# schematic.net
KiCad netlist of a schematic drawn in Altium Designer
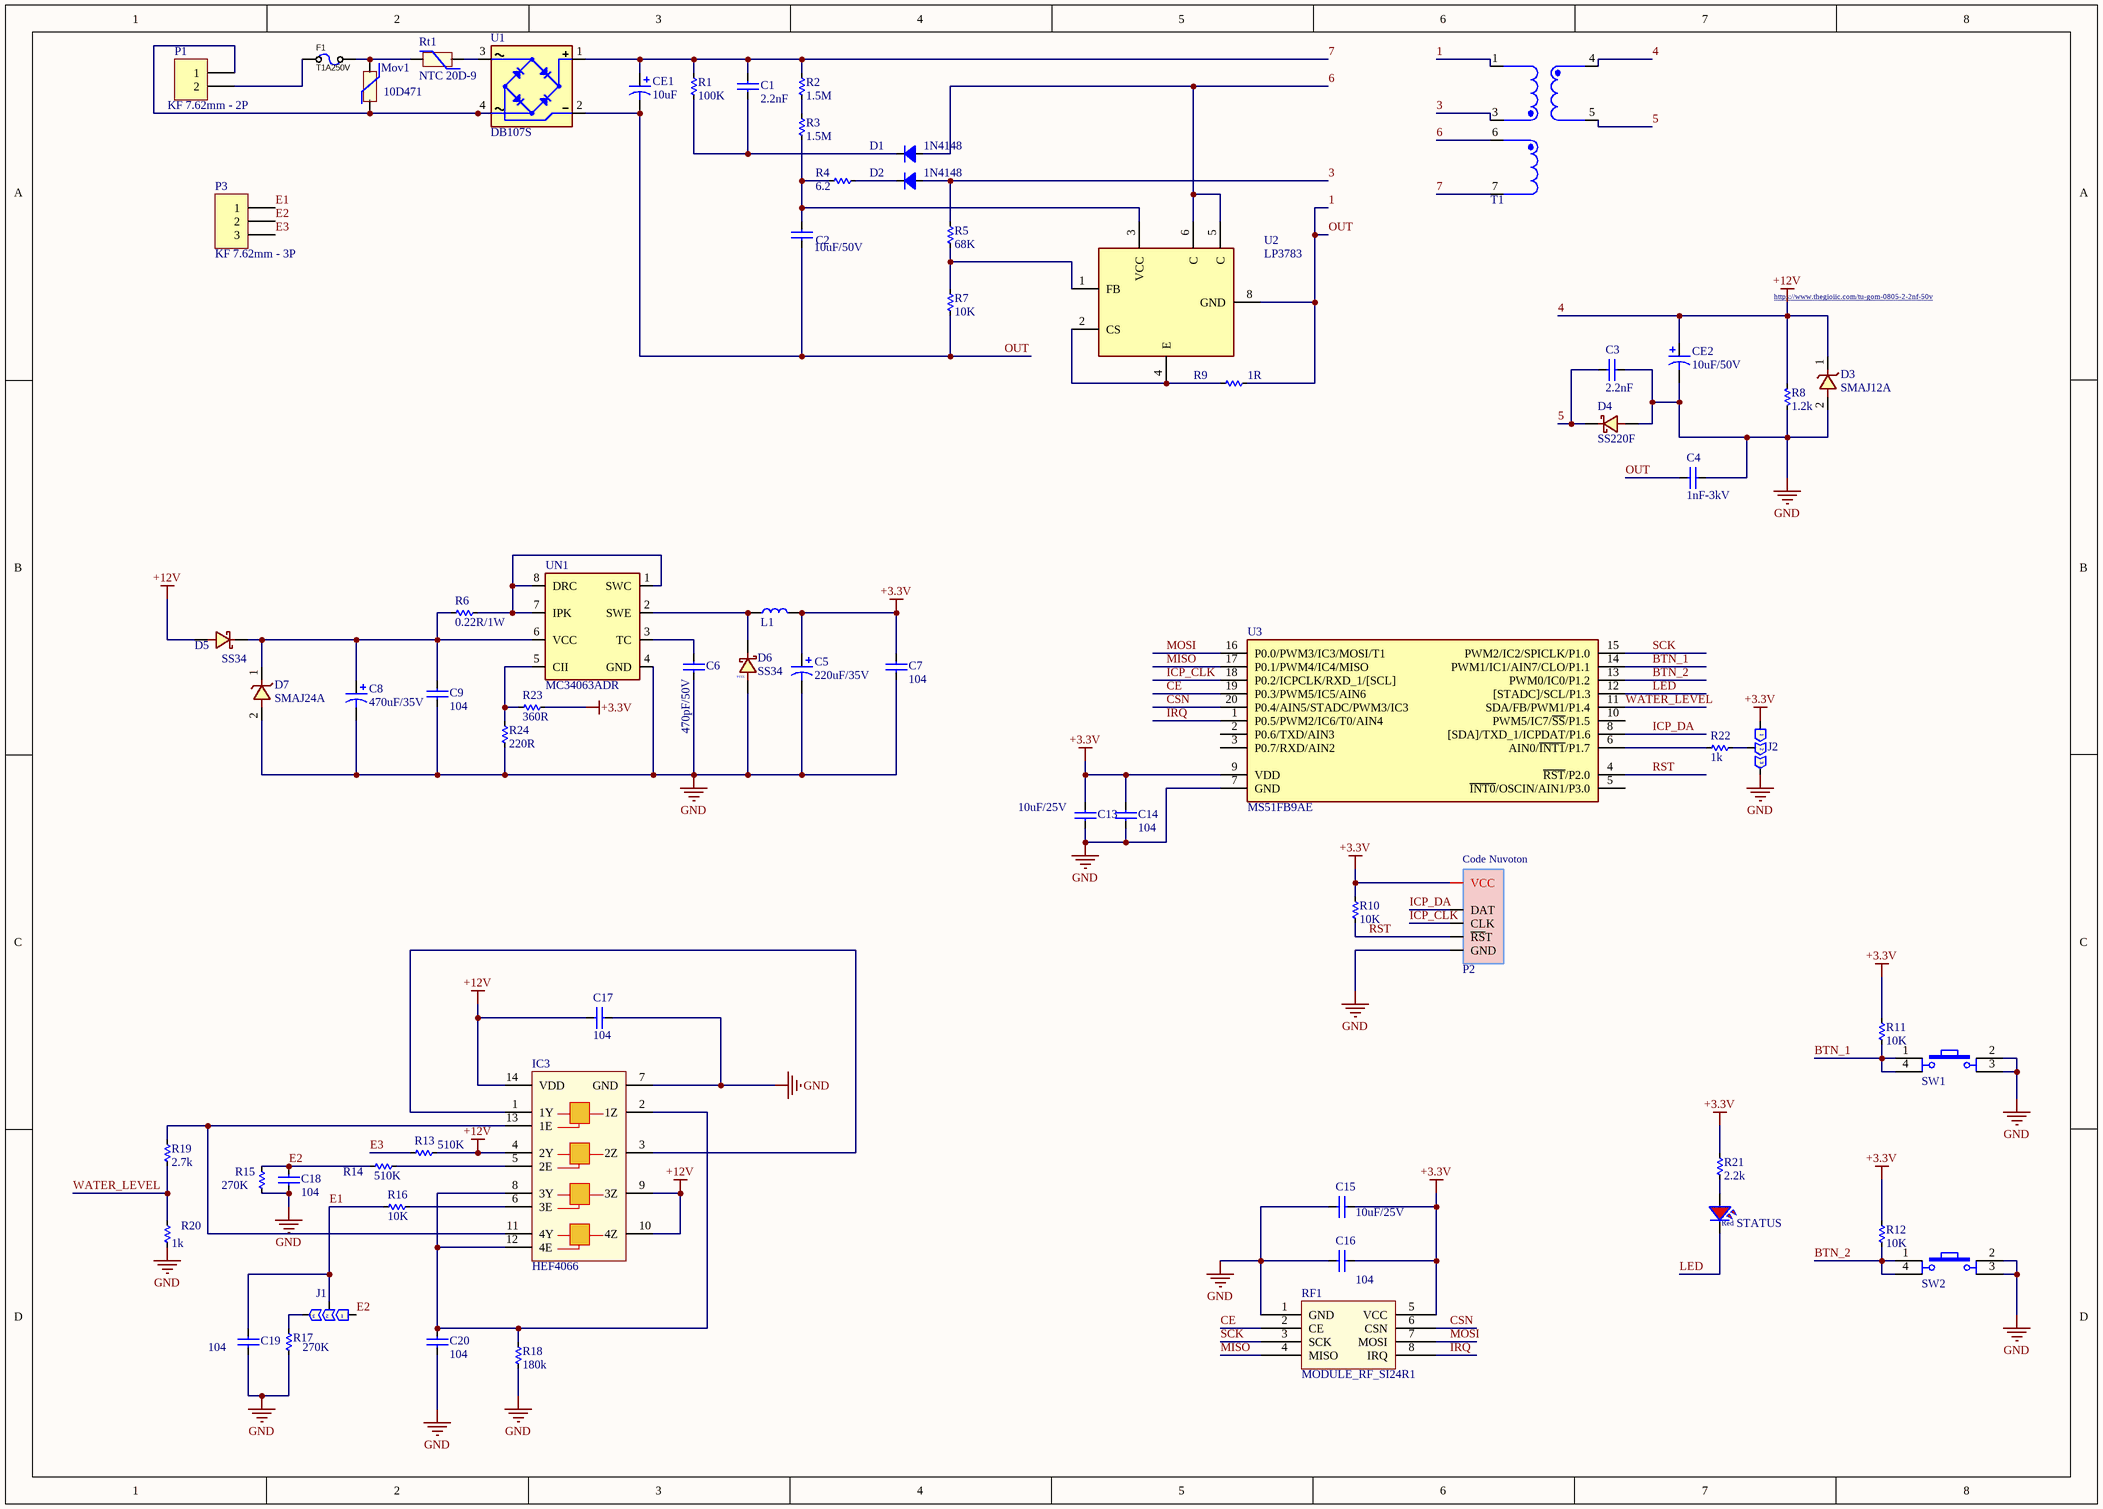
[diagram p0: schematic.SchDoc]

(export (version "E")
  (design (tool "Eeschema 10.0.6"))
  (components
    (comp (ref "C1")
      (value "2.2nF")
      (footprint "C_0805_SMD")
      (description "Tu 2.2nF 50V, SMD 0805")
      (libsource (lib "RD Integrated_Library") (part "Cap 0805 2.2nF 50V"))
    )
    (comp (ref "C2")
      (value "10uF/50V")
      (footprint "C_0805_SMD")
      (description "Cap SMD 0805 10uF 50V")
      (libsource (lib "RD Integrated_Library") (part "Cap 0805 10uF 50V"))
    )
    (comp (ref "C3")
      (value "2.2nF")
      (footprint "C_0805_SMD")
      (description "Tu 2.2nF 50V, SMD 0805")
      (libsource (lib "RD Integrated_Library") (part "Cap 0805 2.2nF 50V"))
    )
    (comp (ref "C4")
      (value "1nF-3kV")
      (footprint "CAP_CERAMIC d5.08")
      (description "102 1KV High Voltage Ceramic Disk Capacitor")
      (libsource (lib "RD Integrated_Library") (part "Cap 1nF 1KV"))
    )
    (comp (ref "C5")
      (value "220uF/35V")
      (footprint "C8X12mm")
      (description "Polarized Capacitor (Axial) 220uF 35V")
      (libsource (lib "RD Integrated_Library") (part "Cap Pol 220uF/35V"))
    )
    (comp (ref "C6")
      (value "470pF/50V")
      (footprint "C_0805_SMD")
      (description "Cap SMD 0805  470pF 50V")
      (libsource (lib "RD Integrated_Library") (part "Cap 0805 470pF 50V"))
    )
    (comp (ref "C7")
      (value "104")
      (footprint "C_0805_SMD")
      (description "Cap SMD 0805 104-100nF-0.1uF 50V")
      (libsource (lib "RD Integrated_Library") (part "Cap 0805 104 100nF"))
    )
    (comp (ref "C8")
      (value "470uF/35V")
      (footprint "C10mm")
      (description "Polarized Capacitor (Axial) 470uF 35V")
      (libsource (lib "RD Integrated_Library") (part "Cap Pol 470uF/35V"))
    )
    (comp (ref "C9")
      (value "104")
      (footprint "C_0805_SMD")
      (description "Cap SMD 0805 104-100nF-0.1uF 50V")
      (libsource (lib "RD Integrated_Library") (part "Cap 0805 104 100nF"))
    )
    (comp (ref "C13")
      (value "10uF/25V")
      (footprint "C_0805_SMD")
      (description "Cap SMD 0805 10uF")
      (libsource (lib "RD Integrated_Library") (part "Cap 0805 10uF 25V"))
    )
    (comp (ref "C14")
      (value "104")
      (footprint "C_0805_SMD")
      (description "Cap SMD 0805 104-100nF-0.1uF 50V")
      (libsource (lib "RD Integrated_Library") (part "Cap 0805 104 100nF"))
    )
    (comp (ref "C15")
      (value "10uF/25V")
      (footprint "C_0805_SMD")
      (description "Cap SMD 0805 10uF")
      (libsource (lib "RD Integrated_Library") (part "Cap 0805 10uF 25V"))
    )
    (comp (ref "C16")
      (value "104")
      (footprint "C_0805_SMD")
      (description "Cap SMD 0805 104-100nF-0.1uF 50V")
      (libsource (lib "RD Integrated_Library") (part "Cap 0805 104 100nF"))
    )
    (comp (ref "C17")
      (value "104")
      (footprint "C_0805_SMD")
      (description "Cap SMD 0805 104-100nF-0.1uF 50V")
      (libsource (lib "RD Integrated_Library") (part "Cap 0805 104 100nF"))
    )
    (comp (ref "C18")
      (value "104")
      (footprint "C_0805_SMD")
      (description "Cap SMD 0805 104-100nF-0.1uF 50V")
      (libsource (lib "RD Integrated_Library") (part "Cap 0805 104 100nF"))
    )
    (comp (ref "C19")
      (value "104")
      (footprint "C_0805_SMD")
      (description "Cap SMD 0805 104-100nF-0.1uF 50V")
      (libsource (lib "RD Integrated_Library") (part "Cap 0805 104 100nF"))
    )
    (comp (ref "C20")
      (value "104")
      (footprint "C_0805_SMD")
      (description "Cap SMD 0805 104-100nF-0.1uF 50V")
      (libsource (lib "RD Integrated_Library") (part "Cap 0805 104 100nF"))
    )
    (comp (ref "CE1")
      (value "10uF")
      (footprint "C_8X12")
      (description "Polarized Capacitor (Axial)")
      (libsource (lib "RD Integrated_Library") (part "Cap Pol 10uF 400V"))
    )
    (comp (ref "CE2")
      (value "10uF/50V")
      (footprint "C5mm")
      (description "Polarized Capacitor (Axial) 10uF/50V")
      (libsource (lib "RD Integrated_Library") (part "Cap Pol 10uF/50V"))
    )
    (comp (ref "D1")
      (value "1N4148")
      (footprint "D_SOD323")
      (description "T4-Rectifier Diode Small Signal Switching 100V 0.25A 4ns 2-Pin SOD-323")
      (libsource (lib "RD Integrated_Library") (part "1N4148WS - T4 SOD-323"))
    )
    (comp (ref "D2")
      (value "1N4148")
      (footprint "D_SOD323")
      (description "T4-Rectifier Diode Small Signal Switching 100V 0.25A 4ns 2-Pin SOD-323")
      (libsource (lib "RD Integrated_Library") (part "1N4148WS - T4 SOD-323"))
    )
    (comp (ref "D3")
      (value "SMAJ12A")
      (footprint "DO_241AC_SMA_MFG")
      (description "SMAJ12A Series 400 W 12 V Surface Mount Uni-Directional TVS Diode - DO-214AC")
      (fields (field (name "DESIGNED BY") "TranLuyen"))
      (libsource (lib "RD Integrated_Library") (part "TVS SMAJ12A-DO241AC"))
    )
    (comp (ref "D4")
      (value "SS220F")
      (footprint "D_SMA")
      (description "200V Independent Type 950mV@2A 2A SMAF Schottky Diodes ROHS")
      (libsource (lib "RD Integrated_Library") (part "SS220F-SMAF"))
    )
    (comp (ref "D5")
      (value "SS34")
      (footprint "D_SMA")
      (description "Surface-Mount Schottky Barrier Rectifier")
      (libsource (lib "RD Integrated_Library") (part "SS34-SMA"))
    )
    (comp (ref "D6")
      (value "SS34")
      (footprint "D_SMA")
      (description "Surface-Mount Schottky Barrier Rectifier")
      (libsource (lib "RD Integrated_Library") (part "SS34-SMA"))
    )
    (comp (ref "D7")
      (value "SMAJ24A")
      (footprint "DO_241AC_SMA_MFG")
      (description "SMAJ Series 400W Surface Mount Uni-Directional TVS Diode - DO-214AC")
      (fields (field (name "DESIGNED BY") "TranLuyen"))
      (libsource (lib "RD Integrated_Library") (part "TVS SMAJ24A-DO241AC"))
    )
    (comp (ref "F1")
      (value "T1A250V")
      (footprint "Fuse 392")
      (libsource (lib "RD Integrated_Library") (part "FUSE 392 T1A250V"))
    )
    (comp (ref "IC3")
      (value "HEF4066")
      (footprint "SO_14")
      (description "HEF4066B Quad single-pole single-throw analog switch")
      (libsource (lib "RD Integrated_Library") (part "HEF4066 SOP-14"))
    )
    (comp (ref "J1")
      (value "JP3-SMD")
      (footprint "J3-SOLDERJUMPER_2WAY_OPEN_NOPASTE")
      (description "SOLDERJUMPER_2WAY_OPEN_NOPASTE")
      (libsource (lib "RD Integrated_Library") (part "Jump 3 SOLDERJUMPER_2WAY_OPEN_NOPASTE"))
    )
    (comp (ref "J2")
      (value "JP3-Close")
      (footprint "JUMP3-CLOSED")
      (description "Jumper, 3-Pin")
      (libsource (lib "RD Integrated_Library") (part "Jump 3 Close"))
    )
    (comp (ref "L1")
      (value "220uH")
      (footprint "CDRH74")
      (description "INDUCTOR SMD")
      (libsource (lib "RD Integrated_Library") (part "CD74 7345-221 220uH"))
    )
    (comp (ref "Mov1")
      (value "10D471")
      (footprint "MOV-10D471")
      (description "MOV-10DxxxK Series - Metal Oxide Varistor")
      (fields (field (name "DESIGNED BY") "TranLuyen"))
      (libsource (lib "RD Integrated_Library") (part "Varistor 10D471K 470V"))
    )
    (comp (ref "P1")
      (value "KF 7.62mm - 2P")
      (footprint "KF 7.62 - 2")
      (fields (field (name "DESIGNED BY") "Tran Luyen"))
      (libsource (lib "RD Integrated_Library") (part "KF 7.62 - 2Pin"))
    )
    (comp (ref "P2")
      (value "Nuvoton")
      (footprint "Header Code Nuvoton 2.54 6P")
      (description "Header 6-5Pin")
      (libsource (lib "RD Integrated_Library") (part "Header Code Nuvoton"))
    )
    (comp (ref "P3")
      (value "KF 7.62mm - 3P")
      (footprint "KF 7.62 - 3")
      (fields (field (name "DESIGNED BY") "Tran Luyen"))
      (libsource (lib "RD Integrated_Library") (part "KF 7.62 - 3P"))
    )
    (comp (ref "R1")
      (value "100K")
      (footprint "RES-SMD-0805")
      (description "Resistor SMD 0805")
      (libsource (lib "RD Integrated_Library") (part "Res 100k 0805"))
    )
    (comp (ref "R2")
      (value "1.5M")
      (footprint "RES-SMD-0805")
      (description "Resistor SMD 0805")
      (libsource (lib "RD Integrated_Library") (part "Res 1.5M 0805"))
    )
    (comp (ref "R3")
      (value "1.5M")
      (footprint "RES-SMD-0805")
      (description "Resistor SMD 0805")
      (libsource (lib "RD Integrated_Library") (part "Res 1.5M 0805"))
    )
    (comp (ref "R4")
      (value "6.2")
      (footprint "RES-SMD-0805")
      (description "Resistor SMD 0805")
      (libsource (lib "RD Integrated_Library") (part "Res 6.2 0805"))
    )
    (comp (ref "R5")
      (value "68K")
      (footprint "RES-SMD-0805")
      (description "Resistor SMD 0805")
      (libsource (lib "RD Integrated_Library") (part "Res 68K 0805"))
    )
    (comp (ref "R6")
      (value "0.22R/1W")
      (footprint "RES-SMD-2512")
      (description "Resistor SMD 2512 1W")
      (libsource (lib "RD Integrated_Library") (part "Res 0.22R 2512 1W"))
    )
    (comp (ref "R7")
      (value "10K")
      (footprint "RES-SMD-0805")
      (description "Resistor SMD 0805")
      (libsource (lib "RD Integrated_Library") (part "Res 10k 0805"))
    )
    (comp (ref "R8")
      (value "1.2k")
      (footprint "RES-SMD-0805")
      (description "Resistor SMD 0805")
      (libsource (lib "RD Integrated_Library") (part "Res 1.2k 0805"))
    )
    (comp (ref "R9")
      (value "1R")
      (footprint "RES-SMD-1206")
      (description "Resistor SMD 1206")
      (libsource (lib "RD Integrated_Library") (part "Res 1R 1206"))
    )
    (comp (ref "R10")
      (value "10K")
      (footprint "RES-SMD-0805")
      (description "Resistor SMD 0805")
      (libsource (lib "RD Integrated_Library") (part "Res 10k 0805"))
    )
    (comp (ref "R11")
      (value "10K")
      (footprint "RES-SMD-0805")
      (description "Resistor SMD 0805")
      (libsource (lib "RD Integrated_Library") (part "Res 10k 0805"))
    )
    (comp (ref "R12")
      (value "10K")
      (footprint "RES-SMD-0805")
      (description "Resistor SMD 0805")
      (libsource (lib "RD Integrated_Library") (part "Res 10k 0805"))
    )
    (comp (ref "R13")
      (value "510K")
      (footprint "RES-SMD-0805")
      (description "Resistor SMD 0805")
      (libsource (lib "RD Integrated_Library") (part "Res 510K 0805"))
    )
    (comp (ref "R14")
      (value "510K")
      (footprint "RES-SMD-0805")
      (description "Resistor SMD 0805")
      (libsource (lib "RD Integrated_Library") (part "Res 510K 0805"))
    )
    (comp (ref "R15")
      (value "270K")
      (footprint "RES-SMD-0805")
      (description "Resistor SMD 0805")
      (libsource (lib "RD Integrated_Library") (part "Res 270K 0805"))
    )
    (comp (ref "R16")
      (value "10K")
      (footprint "RES-SMD-0805")
      (description "Resistor SMD 0805")
      (libsource (lib "RD Integrated_Library") (part "Res 10k 0805"))
    )
    (comp (ref "R17")
      (value "270K")
      (footprint "RES-SMD-0805")
      (description "Resistor SMD 0805")
      (libsource (lib "RD Integrated_Library") (part "Res 270K 0805"))
    )
    (comp (ref "R18")
      (value "180k")
      (footprint "RES-SMD-0805")
      (description "Resistor SMD 0805")
      (libsource (lib "RD Integrated_Library") (part "Res 180K 0805"))
    )
    (comp (ref "R19")
      (value "2.7k")
      (footprint "RES-SMD-0805")
      (description "Resistor SMD 0805")
      (libsource (lib "RD Integrated_Library") (part "Res 2.7K 0805"))
    )
    (comp (ref "R20")
      (value "1k")
      (footprint "RES-SMD-0805")
      (description "Resistor SMD 0805")
      (libsource (lib "RD Integrated_Library") (part "Res 1k 0805"))
    )
    (comp (ref "R21")
      (value "2.2k")
      (footprint "RES-SMD-0805")
      (description "Resistor SMD 0805")
      (libsource (lib "RD Integrated_Library") (part "Res 2.2K 0805"))
    )
    (comp (ref "R22")
      (value "1k")
      (footprint "RES-SMD-0805")
      (description "Resistor SMD 0805")
      (libsource (lib "RD Integrated_Library") (part "Res 1k 0805"))
    )
    (comp (ref "R23")
      (value "360R")
      (footprint "RES-SMD-0805")
      (description "Resistor SMD 0805")
      (libsource (lib "RD Integrated_Library") (part "Res 360R 0805"))
    )
    (comp (ref "R24")
      (value "220R")
      (footprint "RES-SMD-0805")
      (description "Resistor SMD 0805")
      (libsource (lib "RD Integrated_Library") (part "Res 220R 0805"))
    )
    (comp (ref "RF1")
      (value "MODULE_RF_SI24R1")
      (footprint "MODULE-RF-Si24R1")
      (libsource (lib "RD Integrated_Library") (part "MODULE RF SI24R1"))
    )
    (comp (ref "Rt1")
      (value "NTC 20D-9")
      (footprint "NTC 5D-9")
      (description "NTC Thermistor")
      (libsource (lib "RD Integrated_Library") (part "NTC 20D-9"))
    )
    (comp (ref "STATUS")
      (value "LED D5 Red")
      (footprint "LED 5mm RED")
      (description "LED Single colour")
      (libsource (lib "RD Integrated_Library") (part "LED 5mm RED"))
    )
    (comp (ref "SW1")
      (value "BT4")
      (footprint "SW4-DIP 6x6x12")
      (description "Switch button 4 pin 6x6 mm DIP")
      (fields (field (name "DESIGNED BY") "TranLuyen"))
      (libsource (lib "RD Integrated_Library") (part "SW4 DIP 6x6x12mm"))
    )
    (comp (ref "SW2")
      (value "BT4")
      (footprint "SW4-DIP 6x6x12")
      (description "Switch button 4 pin 6x6 mm DIP")
      (fields (field (name "DESIGNED BY") "TranLuyen"))
      (libsource (lib "RD Integrated_Library") (part "SW4 DIP 6x6x12mm"))
    )
    (comp (ref "T1")
      (value "24V-7VA")
      (footprint "EE15")
      (description "Transformer EE15 6 PIN")
      (libsource (lib "RD Integrated_Library") (part "TRANS EE15 5V-2A"))
    )
    (comp (ref "U1")
      (value "DB107S")
      (footprint "DBRG_DIPSMD_MINI")
      (description "BRIDGE RECTIFIER 1KV 1A")
      (fields (field (name "DESIGNED BY") "TranLuyen"))
      (libsource (lib "RD Integrated_Library") (part "MB10F 1KV 0.5A"))
    )
    (comp (ref "U2")
      (value "LP3783")
      (footprint "SO_8")
      (libsource (lib "RD Integrated_Library") (part "LP3783"))
    )
    (comp (ref "U3")
      (value "MS51FB9AE")
      (footprint "SOG65_20")
      (description "MS51FB9AE, ROM 16KB, RAM 256B + 1KB, SPROM 128B, 1T 8051-based CMOS up to 24Mhz")
      (fields (field (name "DESIGNED BY") "Nhox"))
      (libsource (lib "RD Integrated_Library") (part "MS51FB9AE"))
    )
    (comp (ref "UN1")
      (value "MC34063ADR")
      (footprint "SO_8")
      (description "MC3x063A 1.5-A Peak Boost/Buck/Inverting Switching Regulators")
      (fields (field (name "DESIGNED BY") "TranLuyen"))
      (libsource (lib "RD Integrated_Library") (part "MC34063ADR"))
    )
  )
  (nets
    (net (code "1") (name "+3.3V") (class "Default")
      (node (ref "C13") (pin "1") (pinfunction "1_1") (pintype "passive"))
      (node (ref "C14") (pin "1") (pinfunction "1_1") (pintype "passive"))
      (node (ref "C15") (pin "2") (pinfunction "2_2") (pintype "passive"))
      (node (ref "C16") (pin "1") (pinfunction "1_1") (pintype "passive"))
      (node (ref "C5") (pin "1") (pinfunction "1_1") (pintype "passive"))
      (node (ref "C7") (pin "1") (pinfunction "1_1") (pintype "passive"))
      (node (ref "J2") (pin "1") (pinfunction "1_1") (pintype "passive"))
      (node (ref "L1") (pin "2") (pinfunction "2_2") (pintype "passive"))
      (node (ref "P2") (pin "1") (pinfunction "VCC_1") (pintype "passive"))
      (node (ref "R10") (pin "1") (pinfunction "1_1") (pintype "passive"))
      (node (ref "R11") (pin "1") (pinfunction "1_1") (pintype "passive"))
      (node (ref "R12") (pin "1") (pinfunction "1_1") (pintype "passive"))
      (node (ref "R21") (pin "1") (pinfunction "1_1") (pintype "passive"))
      (node (ref "R23") (pin "1") (pinfunction "1_1") (pintype "passive"))
      (node (ref "RF1") (pin "5") (pinfunction "VCC_5") (pintype "passive"))
      (node (ref "U3") (pin "9") (pinfunction "VDD_9") (pintype "passive"))
    )
    (net (code "2") (name "+12V") (class "Default")
      (node (ref "C17") (pin "1") (pinfunction "1_1") (pintype "passive"))
      (node (ref "CE2") (pin "1") (pinfunction "1_1") (pintype "passive"))
      (node (ref "D3") (pin "1") (pinfunction "1_1") (pintype "passive"))
      (node (ref "D5") (pin "1") (pinfunction "A_1") (pintype "passive"))
      (node (ref "IC3") (pin "10") (pinfunction "4Z_10") (pintype "passive"))
      (node (ref "IC3") (pin "14") (pinfunction "VDD_14") (pintype "power_in"))
      (node (ref "IC3") (pin "4") (pinfunction "2Y_4") (pintype "passive"))
      (node (ref "IC3") (pin "9") (pinfunction "3Z_9") (pintype "passive"))
      (node (ref "R13") (pin "1") (pinfunction "1_1") (pintype "passive"))
      (node (ref "R8") (pin "1") (pinfunction "1_1") (pintype "passive"))
      (node (ref "T1") (pin "4") (pinfunction "4_4") (pintype "passive"))
    )
    (net (code "3") (name "/1") (class "Default")
      (node (ref "C2") (pin "2") (pinfunction "2_2") (pintype "passive"))
      (node (ref "C4") (pin "2") (pinfunction "2_2") (pintype "passive"))
      (node (ref "CE1") (pin "2") (pinfunction "2_2") (pintype "passive"))
      (node (ref "R7") (pin "2") (pinfunction "2_2") (pintype "passive"))
      (node (ref "R9") (pin "2") (pinfunction "2_2") (pintype "passive"))
      (node (ref "T1") (pin "1") (pinfunction "1_1") (pintype "passive"))
      (node (ref "U1") (pin "2") (pinfunction "DCOUT-_2") (pintype "passive"))
      (node (ref "U2") (pin "8") (pinfunction "GND_8") (pintype "passive"))
    )
    (net (code "4") (name "/3") (class "Default")
      (node (ref "D2") (pin "1") (pinfunction "1_1") (pintype "passive"))
      (node (ref "R5") (pin "1") (pinfunction "1_1") (pintype "passive"))
      (node (ref "T1") (pin "3") (pinfunction "3_3") (pintype "passive"))
    )
    (net (code "5") (name "/5") (class "Default")
      (node (ref "C3") (pin "1") (pinfunction "1_1") (pintype "passive"))
      (node (ref "D4") (pin "2") (pinfunction "K_2") (pintype "passive"))
      (node (ref "T1") (pin "5") (pinfunction "5_5") (pintype "passive"))
    )
    (net (code "6") (name "/6") (class "Default")
      (node (ref "D1") (pin "1") (pinfunction "1_1") (pintype "passive"))
      (node (ref "T1") (pin "6") (pinfunction "6_6") (pintype "passive"))
      (node (ref "U2") (pin "5") (pinfunction "C_5") (pintype "passive"))
      (node (ref "U2") (pin "6") (pinfunction "C_6") (pintype "passive"))
    )
    (net (code "7") (name "/7") (class "Default")
      (node (ref "C1") (pin "2") (pinfunction "2_2") (pintype "passive"))
      (node (ref "CE1") (pin "1") (pinfunction "1_1") (pintype "passive"))
      (node (ref "R1") (pin "1") (pinfunction "1_1") (pintype "passive"))
      (node (ref "R2") (pin "1") (pinfunction "1_1") (pintype "passive"))
      (node (ref "T1") (pin "7") (pinfunction "7_7") (pintype "passive"))
      (node (ref "U1") (pin "1") (pinfunction "DCOUT+_1") (pintype "passive"))
    )
    (net (code "8") (name "/BTN_1") (class "Default")
      (node (ref "R11") (pin "2") (pinfunction "2_2") (pintype "passive"))
      (node (ref "SW1") (pin "1") (pintype "passive"))
      (node (ref "SW1") (pin "4") (pintype "passive"))
      (node (ref "U3") (pin "14") (pinfunction "PWM1/IC1/AIN7/CLO/P1.1_14") (pintype "passive"))
    )
    (net (code "9") (name "/BTN_2") (class "Default")
      (node (ref "R12") (pin "2") (pinfunction "2_2") (pintype "passive"))
      (node (ref "SW2") (pin "1") (pintype "passive"))
      (node (ref "SW2") (pin "4") (pintype "passive"))
      (node (ref "U3") (pin "13") (pinfunction "PWM0/IC0/P1.2_13") (pintype "passive"))
    )
    (net (code "10") (name "/CE") (class "Default")
      (node (ref "RF1") (pin "2") (pinfunction "CE_2") (pintype "passive"))
      (node (ref "U3") (pin "19") (pinfunction "P0.3/PWM5/IC5/AIN6_19") (pintype "passive"))
    )
    (net (code "11") (name "/CSN") (class "Default")
      (node (ref "RF1") (pin "6") (pinfunction "CSN_6") (pintype "passive"))
      (node (ref "U3") (pin "20") (pinfunction "P0.4/AIN5/STADC/PWM3/IC3_20") (pintype "passive"))
    )
    (net (code "12") (name "/E1") (class "Default")
      (node (ref "C19") (pin "2") (pinfunction "2_2") (pintype "passive"))
      (node (ref "J1") (pin "2") (pinfunction "2_2") (pintype "passive"))
      (node (ref "P3") (pin "1") (pinfunction "1_1") (pintype "passive"))
      (node (ref "R16") (pin "2") (pinfunction "2_2") (pintype "passive"))
    )
    (net (code "13") (name "/E2") (class "Default")
      (node (ref "C18") (pin "2") (pinfunction "2_2") (pintype "passive"))
      (node (ref "J1") (pin "1") (pinfunction "1_1") (pintype "passive"))
      (node (ref "P3") (pin "2") (pinfunction "2_2") (pintype "passive"))
      (node (ref "R14") (pin "2") (pinfunction "2_2") (pintype "passive"))
      (node (ref "R15") (pin "1") (pinfunction "1_1") (pintype "passive"))
    )
    (net (code "14") (name "/E3") (class "Default")
      (node (ref "P3") (pin "3") (pinfunction "3_3") (pintype "passive"))
      (node (ref "R13") (pin "2") (pinfunction "2_2") (pintype "passive"))
    )
    (net (code "15") (name "/ICP_CLK") (class "Default")
      (node (ref "P2") (pin "4") (pinfunction "CLK_4") (pintype "passive"))
      (node (ref "U3") (pin "18") (pinfunction "P0.2/ICPCLK/RXD_1/[SCL]_18") (pintype "passive"))
    )
    (net (code "16") (name "/ICP_DA") (class "Default")
      (node (ref "P2") (pin "3") (pinfunction "DAT_3") (pintype "passive"))
      (node (ref "U3") (pin "8") (pinfunction "[SDA]/TXD_1/ICPDAT/P1.6_8") (pintype "passive"))
    )
    (net (code "17") (name "/IRQ") (class "Default")
      (node (ref "RF1") (pin "8") (pinfunction "IRQ_8") (pintype "passive"))
      (node (ref "U3") (pin "1") (pinfunction "P0.5/PWM2/IC6/T0/AIN4_1") (pintype "passive"))
    )
    (net (code "18") (name "/LED") (class "Default")
      (node (ref "STATUS") (pin "2") (pinfunction "2_2") (pintype "passive"))
      (node (ref "U3") (pin "12") (pinfunction "[STADC]/SCL/P1.3_12") (pintype "passive"))
    )
    (net (code "19") (name "/MISO") (class "Default")
      (node (ref "RF1") (pin "4") (pinfunction "MISO_4") (pintype "passive"))
      (node (ref "U3") (pin "17") (pinfunction "P0.1/PWM4/IC4/MISO_17") (pintype "passive"))
    )
    (net (code "20") (name "/MOSI") (class "Default")
      (node (ref "RF1") (pin "7") (pinfunction "MOSI_7") (pintype "passive"))
      (node (ref "U3") (pin "16") (pinfunction "P0.0/PWM3/IC3/MOSI/T1_16") (pintype "passive"))
    )
    (net (code "21") (name "/RST") (class "Default")
      (node (ref "P2") (pin "5") (pinfunction "~{RS}T_5") (pintype "passive"))
      (node (ref "R10") (pin "2") (pinfunction "2_2") (pintype "passive"))
      (node (ref "U3") (pin "4") (pinfunction "~{RST}/P2.0_4") (pintype "passive"))
    )
    (net (code "22") (name "/SCK") (class "Default")
      (node (ref "RF1") (pin "3") (pinfunction "SCK_3") (pintype "passive"))
      (node (ref "U3") (pin "15") (pinfunction "PWM2/IC2/SPICLK/P1.0_15") (pintype "passive"))
    )
    (net (code "23") (name "/WATER_LEVEL") (class "Default")
      (node (ref "R19") (pin "2") (pinfunction "2_2") (pintype "passive"))
      (node (ref "R20") (pin "1") (pinfunction "1_1") (pintype "passive"))
      (node (ref "U3") (pin "11") (pinfunction "SDA/FB/PWM1/P1.4_11") (pintype "passive"))
    )
    (net (code "24") (name "GND") (class "Default")
      (node (ref "C13") (pin "2") (pinfunction "2_2") (pintype "passive"))
      (node (ref "C14") (pin "2") (pinfunction "2_2") (pintype "passive"))
      (node (ref "C15") (pin "1") (pinfunction "1_1") (pintype "passive"))
      (node (ref "C16") (pin "2") (pinfunction "2_2") (pintype "passive"))
      (node (ref "C17") (pin "2") (pinfunction "2_2") (pintype "passive"))
      (node (ref "C18") (pin "1") (pinfunction "1_1") (pintype "passive"))
      (node (ref "C19") (pin "1") (pinfunction "1_1") (pintype "passive"))
      (node (ref "C20") (pin "1") (pinfunction "1_1") (pintype "passive"))
      (node (ref "C3") (pin "2") (pinfunction "2_2") (pintype "passive"))
      (node (ref "C4") (pin "1") (pinfunction "1_1") (pintype "passive"))
      (node (ref "C5") (pin "2") (pinfunction "2_2") (pintype "passive"))
      (node (ref "C6") (pin "1") (pinfunction "1_1") (pintype "passive"))
      (node (ref "C7") (pin "2") (pinfunction "2_2") (pintype "passive"))
      (node (ref "C8") (pin "2") (pinfunction "2_2") (pintype "passive"))
      (node (ref "C9") (pin "1") (pinfunction "1_1") (pintype "passive"))
      (node (ref "CE2") (pin "2") (pinfunction "2_2") (pintype "passive"))
      (node (ref "D3") (pin "2") (pinfunction "2_2") (pintype "passive"))
      (node (ref "D4") (pin "1") (pinfunction "A_1") (pintype "passive"))
      (node (ref "D6") (pin "1") (pinfunction "A_1") (pintype "passive"))
      (node (ref "D7") (pin "2") (pinfunction "2_2") (pintype "passive"))
      (node (ref "IC3") (pin "7") (pinfunction "GND_7") (pintype "passive"))
      (node (ref "J2") (pin "3") (pinfunction "3_3") (pintype "passive"))
      (node (ref "P2") (pin "6") (pinfunction "GND_6") (pintype "passive"))
      (node (ref "R15") (pin "2") (pinfunction "2_2") (pintype "passive"))
      (node (ref "R17") (pin "2") (pinfunction "2_2") (pintype "passive"))
      (node (ref "R18") (pin "2") (pinfunction "2_2") (pintype "passive"))
      (node (ref "R20") (pin "2") (pinfunction "2_2") (pintype "passive"))
      (node (ref "R24") (pin "2") (pinfunction "2_2") (pintype "passive"))
      (node (ref "R8") (pin "2") (pinfunction "2_2") (pintype "passive"))
      (node (ref "RF1") (pin "1") (pinfunction "GND_1") (pintype "passive"))
      (node (ref "SW1") (pin "2") (pintype "passive"))
      (node (ref "SW1") (pin "3") (pintype "passive"))
      (node (ref "SW2") (pin "2") (pintype "passive"))
      (node (ref "SW2") (pin "3") (pintype "passive"))
      (node (ref "U3") (pin "7") (pinfunction "GND_7") (pintype "passive"))
      (node (ref "UN1") (pin "4") (pinfunction "GND_4") (pintype "passive"))
    )
    (net (code "25") (name "Net-(C1-Pad1)") (class "Default")
      (node (ref "C1") (pin "1") (pinfunction "1_1") (pintype "passive"))
      (node (ref "D1") (pin "2") (pinfunction "2_2") (pintype "passive"))
      (node (ref "R1") (pin "2") (pinfunction "2_2") (pintype "passive"))
    )
    (net (code "26") (name "Net-(D2-Pad2)") (class "Default")
      (node (ref "D2") (pin "2") (pinfunction "2_2") (pintype "passive"))
      (node (ref "R4") (pin "2") (pinfunction "2_2") (pintype "passive"))
    )
    (net (code "27") (name "Net-(D5-K)") (class "Default")
      (node (ref "C8") (pin "1") (pinfunction "1_1") (pintype "passive"))
      (node (ref "C9") (pin "2") (pinfunction "2_2") (pintype "passive"))
      (node (ref "D5") (pin "2") (pinfunction "K_2") (pintype "passive"))
      (node (ref "D7") (pin "1") (pinfunction "1_1") (pintype "passive"))
      (node (ref "R6") (pin "2") (pinfunction "2_2") (pintype "passive"))
      (node (ref "UN1") (pin "6") (pinfunction "VCC_6") (pintype "passive"))
    )
    (net (code "28") (name "Net-(D6-K)") (class "Default")
      (node (ref "D6") (pin "2") (pinfunction "K_2") (pintype "passive"))
      (node (ref "L1") (pin "1") (pinfunction "1_1") (pintype "passive"))
      (node (ref "UN1") (pin "2") (pinfunction "SWE_2") (pintype "passive"))
    )
    (net (code "29") (name "Net-(F1-Pad1)") (class "Default")
      (node (ref "F1") (pin "1") (pinfunction "1_1") (pintype "passive"))
      (node (ref "P1") (pin "2") (pinfunction "2_2") (pintype "passive"))
    )
    (net (code "30") (name "Net-(F1-Pad2)") (class "Default")
      (node (ref "F1") (pin "2") (pinfunction "2_2") (pintype "passive"))
      (node (ref "Mov1") (pin "1") (pinfunction "1_1") (pintype "passive"))
      (node (ref "Rt1") (pin "2") (pinfunction "2_2") (pintype "passive"))
    )
    (net (code "31") (name "Net-(IC3-1E)") (class "Default")
      (node (ref "IC3") (pin "11") (pinfunction "4Y_11") (pintype "passive"))
      (node (ref "IC3") (pin "13") (pinfunction "1E_13") (pintype "passive"))
      (node (ref "R19") (pin "1") (pinfunction "1_1") (pintype "passive"))
    )
    (net (code "32") (name "Net-(IC3-1Y)") (class "Default")
      (node (ref "IC3") (pin "1") (pinfunction "1Y_1") (pintype "passive"))
      (node (ref "IC3") (pin "3") (pinfunction "2Z_3") (pintype "passive"))
    )
    (net (code "33") (name "Net-(IC3-1Z)") (class "Default")
      (node (ref "C20") (pin "2") (pinfunction "2_2") (pintype "passive"))
      (node (ref "IC3") (pin "12") (pinfunction "4E_12") (pintype "passive"))
      (node (ref "IC3") (pin "2") (pinfunction "1Z_2") (pintype "passive"))
      (node (ref "IC3") (pin "8") (pinfunction "3Y_8") (pintype "passive"))
      (node (ref "R18") (pin "1") (pinfunction "1_1") (pintype "passive"))
    )
    (net (code "34") (name "Net-(IC3-2E)") (class "Default")
      (node (ref "IC3") (pin "5") (pinfunction "2E_5") (pintype "passive"))
      (node (ref "R14") (pin "1") (pinfunction "1_1") (pintype "passive"))
    )
    (net (code "35") (name "Net-(IC3-3E)") (class "Default")
      (node (ref "IC3") (pin "6") (pinfunction "3E_6") (pintype "passive"))
      (node (ref "R16") (pin "1") (pinfunction "1_1") (pintype "passive"))
    )
    (net (code "36") (name "Net-(J1-Pad3)") (class "Default")
      (node (ref "J1") (pin "3") (pinfunction "3_3") (pintype "passive"))
      (node (ref "R17") (pin "1") (pinfunction "1_1") (pintype "passive"))
    )
    (net (code "37") (name "Net-(J2-Pad2)") (class "Default")
      (node (ref "J2") (pin "2") (pinfunction "2_2") (pintype "passive"))
      (node (ref "R22") (pin "1") (pinfunction "1_1") (pintype "passive"))
    )
    (net (code "38") (name "Net-(R2-Pad2)") (class "Default")
      (node (ref "R2") (pin "2") (pinfunction "2_2") (pintype "passive"))
      (node (ref "R3") (pin "1") (pinfunction "1_1") (pintype "passive"))
    )
    (net (code "39") (name "Net-(R21-Pad2)") (class "Default")
      (node (ref "R21") (pin "2") (pinfunction "2_2") (pintype "passive"))
      (node (ref "STATUS") (pin "1") (pinfunction "1_1") (pintype "passive"))
    )
    (net (code "40") (name "Net-(U1-ACIN1)") (class "Default")
      (node (ref "Mov1") (pin "2") (pinfunction "2_2") (pintype "passive"))
      (node (ref "P1") (pin "1") (pinfunction "1_1") (pintype "passive"))
      (node (ref "U1") (pin "4") (pinfunction "ACIN1_4") (pintype "passive"))
    )
    (net (code "41") (name "Net-(U1-ACIN2)") (class "Default")
      (node (ref "Rt1") (pin "1") (pinfunction "1_1") (pintype "passive"))
      (node (ref "U1") (pin "3") (pinfunction "ACIN2_3") (pintype "passive"))
    )
    (net (code "42") (name "Net-(U2-CS)") (class "Default")
      (node (ref "R9") (pin "1") (pinfunction "1_1") (pintype "passive"))
      (node (ref "U2") (pin "2") (pinfunction "CS_2") (pintype "passive"))
      (node (ref "U2") (pin "4") (pinfunction "E_4") (pintype "passive"))
    )
    (net (code "43") (name "Net-(U2-FB)") (class "Default")
      (node (ref "R5") (pin "2") (pinfunction "2_2") (pintype "passive"))
      (node (ref "R7") (pin "1") (pinfunction "1_1") (pintype "passive"))
      (node (ref "U2") (pin "1") (pinfunction "FB_1") (pintype "passive"))
    )
    (net (code "44") (name "Net-(U2-VCC)") (class "Default")
      (node (ref "C2") (pin "1") (pinfunction "1_1") (pintype "passive"))
      (node (ref "R3") (pin "2") (pinfunction "2_2") (pintype "passive"))
      (node (ref "R4") (pin "1") (pinfunction "1_1") (pintype "passive"))
      (node (ref "U2") (pin "3") (pinfunction "VCC_3") (pintype "passive"))
    )
    (net (code "45") (name "Net-(U3-AIN0{slash}~{INT1}{slash}P1.7)") (class "Default")
      (node (ref "R22") (pin "2") (pinfunction "2_2") (pintype "passive"))
      (node (ref "U3") (pin "6") (pinfunction "AIN0/~{INT1}/P1.7_6") (pintype "passive"))
    )
    (net (code "46") (name "Net-(UN1-CII)") (class "Default")
      (node (ref "R23") (pin "2") (pinfunction "2_2") (pintype "passive"))
      (node (ref "R24") (pin "1") (pinfunction "1_1") (pintype "passive"))
      (node (ref "UN1") (pin "5") (pinfunction "CII_5") (pintype "passive"))
    )
    (net (code "47") (name "Net-(UN1-DRC)") (class "Default")
      (node (ref "R6") (pin "1") (pinfunction "1_1") (pintype "passive"))
      (node (ref "UN1") (pin "1") (pinfunction "SWC_1") (pintype "passive"))
      (node (ref "UN1") (pin "7") (pinfunction "IPK_7") (pintype "passive"))
      (node (ref "UN1") (pin "8") (pinfunction "DRC_8") (pintype "passive"))
    )
    (net (code "48") (name "Net-(UN1-TC)") (class "Default")
      (node (ref "C6") (pin "2") (pinfunction "2_2") (pintype "passive"))
      (node (ref "UN1") (pin "3") (pinfunction "TC_3") (pintype "passive"))
    )
    (net (code "49") (name "unconnected-(U3-P0.6{slash}TXD{slash}AIN3-Pad2)") (class "Default")
      (node (ref "U3") (pin "2") (pinfunction "P0.6/TXD/AIN3_2") (pintype "passive"))
    )
    (net (code "50") (name "unconnected-(U3-P0.7{slash}RXD{slash}AIN2-Pad3)") (class "Default")
      (node (ref "U3") (pin "3") (pinfunction "P0.7/RXD/AIN2_3") (pintype "passive"))
    )
    (net (code "51") (name "unconnected-(U3-PWM5{slash}IC7{slash}~{SS}{slash}P1.5-Pad10)") (class "Default")
      (node (ref "U3") (pin "10") (pinfunction "PWM5/IC7/~{SS}/P1.5_10") (pintype "passive"))
    )
    (net (code "52") (name "unconnected-(U3-~{INT0}{slash}OSCIN{slash}AIN1{slash}P3.0-Pad5)") (class "Default")
      (node (ref "U3") (pin "5") (pinfunction "~{INT0}/OSCIN/AIN1/P3.0_5") (pintype "passive"))
    )
  )
)
